# ProPrj___2025-12-14-15-51-23.net
KiCad netlist of a schematic drawn in EasyEDA Pro
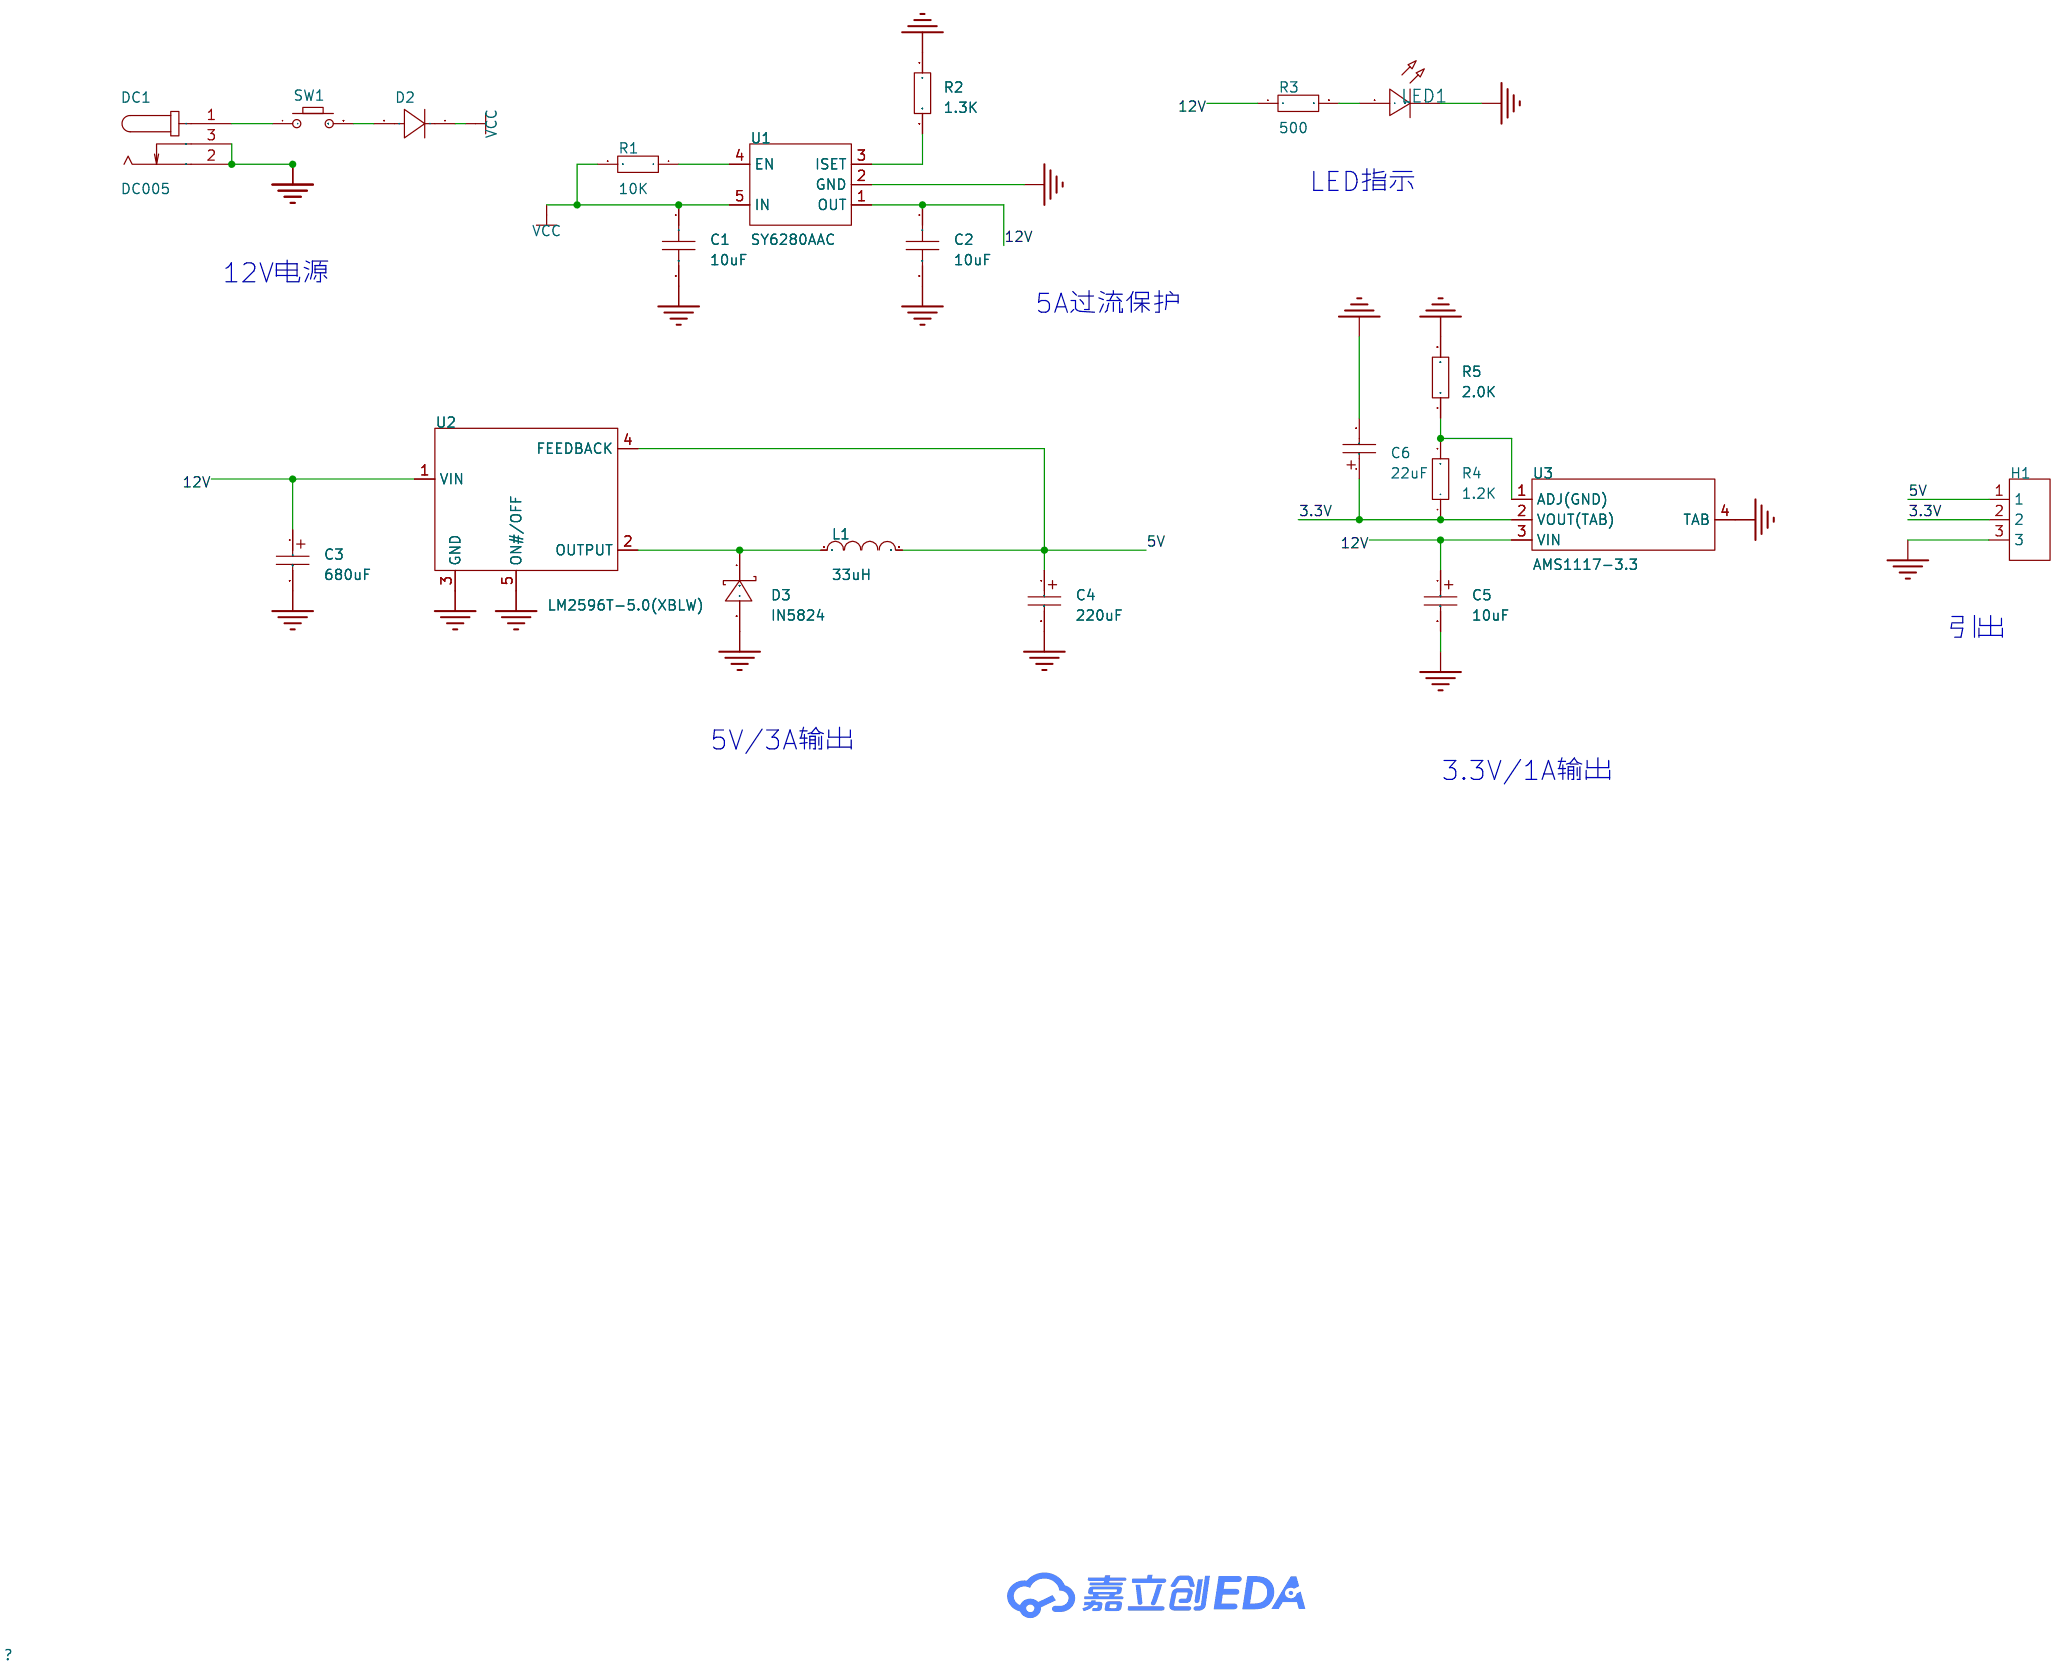
[diagram p0: schematic sheet]

(export (version "E")
  (design (tool "Eeschema 10.0.6"))
  (components
    (comp (ref "C1")
      (value "10uF")
      (footprint "easyedapro:C0603")
      (libsource (lib "easyedapro") (part "Capacitance"))
    )
    (comp (ref "C2")
      (value "10uF")
      (footprint "easyedapro:C0603")
      (libsource (lib "easyedapro") (part "Capacitance"))
    )
    (comp (ref "C3")
      (value "680uF")
      (footprint "easyedapro:C_Ele_SMD_3x5.4mm")
      (libsource (lib "easyedapro") (part "CAP"))
    )
    (comp (ref "C4")
      (value "220uF")
      (footprint "easyedapro:C_Ele_SMD_3x5.4mm")
      (libsource (lib "easyedapro") (part "CAP"))
    )
    (comp (ref "C5")
      (value "10uF")
      (footprint "easyedapro:C_Ele_SMD_3x5.4mm")
      (libsource (lib "easyedapro") (part "CAP"))
    )
    (comp (ref "C6")
      (value "22uF")
      (footprint "easyedapro:C_Ele_SMD_3x5.4mm")
      (libsource (lib "easyedapro") (part "CAP"))
    )
    (comp (ref "D2")
      (value "~")
      (footprint "easyedapro:DO_1N4007")
      (libsource (lib "easyedapro") (part "D_1N4007"))
    )
    (comp (ref "D3")
      (value "IN5824")
      (footprint "easyedapro:SMAF_L3.5-W2.6-LS4.7-RD")
      (libsource (lib "easyedapro") (part "IN5824"))
    )
    (comp (ref "DC1")
      (value "DC005")
      (footprint "easyedapro:DC-IN-TH_DC005")
      (description "连接器类型:DC电源插座;安装方式:弯插;触点内径:2mm;触点外径:6.3mm;额定电流:500mA;额定电压:12V;工作温度:-30°C~+70°C;")
      (fields (field (name "Manufacturer") "SHOU HAN(首韩)"))
      (libsource (lib "easyedapro") (part "DC005_C431533"))
    )
    (comp (ref "H1")
      (value "~")
      (footprint "easyedapro:HDR-TH_3P-P2.54-V-F")
      (libsource (lib "easyedapro") (part "PM254V-11-03-H85"))
    )
    (comp (ref "L1")
      (value "33uH")
      (footprint "easyedapro:L0603")
      (libsource (lib "easyedapro") (part "SDFL1608S100KTF"))
    )
    (comp (ref "LED1")
      (value "~")
      (footprint "easyedapro:LED_0603")
      (libsource (lib "easyedapro") (part "LED_R"))
    )
    (comp (ref "R1") (value "10K") (footprint "easyedapro:R0603") (libsource (lib "easyedapro") (part "电阻")))
    (comp (ref "R2") (value "1.3K") (footprint "easyedapro:R0603") (libsource (lib "easyedapro") (part "电阻")))
    (comp (ref "R3") (value "500") (footprint "easyedapro:R0603") (libsource (lib "easyedapro") (part "电阻")))
    (comp (ref "R4") (value "1.2K") (footprint "easyedapro:R0603") (libsource (lib "easyedapro") (part "电阻")))
    (comp (ref "R5") (value "2.0K") (footprint "easyedapro:R0603") (libsource (lib "easyedapro") (part "电阻")))
    (comp (ref "SW1")
      (value "~")
      (footprint "easyedapro:Key_TH_3.5x6x4.3")
      (libsource (lib "easyedapro") (part "Key_TH_3.5x6x4.3"))
    )
    (comp (ref "U1")
      (value "SY6280AAC")
      (footprint "easyedapro:SOT-23-5_L3.0-W1.7-P0.95-LS2.8-BR")
      (libsource (lib "easyedapro") (part "SY6280AAC_C9900003867"))
    )
    (comp (ref "U2")
      (value "LM2596T-5.0(XBLW)")
      (footprint "easyedapro:TO-220-5L_L10.2-W4.5-P1.71-L")
      (description "功能类型:降压型;工作电压:6V~40V;输出电压:5V;输出电流:3A;输出类型:固定;")
      (fields (field (name "Manufacturer") "XBLW(芯伯乐)"))
      (libsource (lib "easyedapro") (part "LM2596T-5.0(XBLW)"))
    )
    (comp (ref "U3")
      (value "AMS1117-3.3")
      (footprint "easyedapro:SOT-223-4_L6.5-W3.5-P2.30-LS7.0-BR")
      (description "输出类型:固定;工作电压:12V;输出电压:3.3V;输出电流:1A;电源纹波抑制比(PSRR):60dB@(120Hz);输出极性:正极;")
      (fields (field (name "Manufacturer") "UMW(友台半导体)"))
      (libsource (lib "easyedapro") (part "AMS1117-3.3_C347222"))
    )
  )
  (nets
    (net (code "1") (name "/3.3V") (class "Default")
      (node (ref "C6") (pin "1") (pinfunction "1_1") (pintype "input"))
      (node (ref "H1") (pin "2") (pinfunction "2_2") (pintype "unspecified"))
      (node (ref "R4") (pin "1") (pinfunction "1_1") (pintype "input"))
      (node (ref "U3") (pin "2") (pinfunction "VOUT(TAB)_2") (pintype "unspecified"))
    )
    (net (code "2") (name "/5V") (class "Default")
      (node (ref "C4") (pin "1") (pinfunction "1_1") (pintype "input"))
      (node (ref "H1") (pin "1") (pinfunction "1_1") (pintype "unspecified"))
      (node (ref "L1") (pin "2") (pinfunction "2_2") (pintype "unspecified"))
      (node (ref "U2") (pin "4") (pinfunction "FEEDBACK_4") (pintype "unspecified"))
    )
    (net (code "3") (name "/12V") (class "Default")
      (node (ref "C2") (pin "1") (pinfunction "1_1") (pintype "input"))
      (node (ref "C3") (pin "1") (pinfunction "1_1") (pintype "input"))
      (node (ref "C5") (pin "1") (pinfunction "1_1") (pintype "input"))
      (node (ref "R3") (pin "1") (pinfunction "1_1") (pintype "input"))
      (node (ref "U1") (pin "1") (pinfunction "OUT_1") (pintype "unspecified"))
      (node (ref "U2") (pin "1") (pinfunction "VIN_1") (pintype "unspecified"))
      (node (ref "U3") (pin "3") (pinfunction "VIN_3") (pintype "unspecified"))
    )
    (net (code "4") (name "GND") (class "Default")
      (node (ref "C1") (pin "2") (pinfunction "2_2") (pintype "input"))
      (node (ref "C2") (pin "2") (pinfunction "2_2") (pintype "input"))
      (node (ref "C3") (pin "2") (pinfunction "2_2") (pintype "input"))
      (node (ref "C4") (pin "2") (pinfunction "2_2") (pintype "input"))
      (node (ref "C5") (pin "2") (pinfunction "2_2") (pintype "input"))
      (node (ref "C6") (pin "2") (pinfunction "2_2") (pintype "input"))
      (node (ref "D3") (pin "2") (pinfunction "A_2") (pintype "unspecified"))
      (node (ref "DC1") (pin "2") (pinfunction "2_2") (pintype "unspecified"))
      (node (ref "DC1") (pin "3") (pinfunction "3_3") (pintype "unspecified"))
      (node (ref "H1") (pin "3") (pinfunction "3_3") (pintype "unspecified"))
      (node (ref "LED1") (pin "1") (pinfunction "C_1") (pintype "input"))
      (node (ref "R2") (pin "1") (pinfunction "1_1") (pintype "input"))
      (node (ref "R5") (pin "2") (pinfunction "2_2") (pintype "input"))
      (node (ref "U1") (pin "2") (pinfunction "GND_2") (pintype "unspecified"))
      (node (ref "U2") (pin "3") (pinfunction "GND_3") (pintype "unspecified"))
      (node (ref "U2") (pin "5") (pinfunction "ON#/OFF_5") (pintype "unspecified"))
      (node (ref "U3") (pin "4") (pinfunction "TAB_4") (pintype "unspecified"))
    )
    (net (code "5") (name "Net-(D2-A)") (class "Default")
      (node (ref "D2") (pin "2") (pinfunction "A_2") (pintype "input"))
      (node (ref "SW1") (pin "B") (pinfunction "B_B") (pintype "input"))
    )
    (net (code "6") (name "Net-(D3-C)") (class "Default")
      (node (ref "D3") (pin "1") (pinfunction "C_1") (pintype "unspecified"))
      (node (ref "L1") (pin "1") (pinfunction "1_1") (pintype "unspecified"))
      (node (ref "U2") (pin "2") (pinfunction "OUTPUT_2") (pintype "unspecified"))
    )
    (net (code "7") (name "Net-(DC1-Pad1)") (class "Default")
      (node (ref "DC1") (pin "1") (pinfunction "1_1") (pintype "unspecified"))
      (node (ref "SW1") (pin "A") (pinfunction "A_A") (pintype "input"))
    )
    (net (code "8") (name "Net-(LED1-A)") (class "Default")
      (node (ref "LED1") (pin "2") (pinfunction "A_2") (pintype "input"))
      (node (ref "R3") (pin "2") (pinfunction "2_2") (pintype "input"))
    )
    (net (code "9") (name "Net-(U1-EN)") (class "Default")
      (node (ref "R1") (pin "1") (pinfunction "1_1") (pintype "input"))
      (node (ref "U1") (pin "4") (pinfunction "EN_4") (pintype "unspecified"))
    )
    (net (code "10") (name "Net-(U1-ISET)") (class "Default")
      (node (ref "R2") (pin "2") (pinfunction "2_2") (pintype "input"))
      (node (ref "U1") (pin "3") (pinfunction "ISET_3") (pintype "unspecified"))
    )
    (net (code "11") (name "Net-(U3-ADJ(GND))") (class "Default")
      (node (ref "R4") (pin "2") (pinfunction "2_2") (pintype "input"))
      (node (ref "R5") (pin "1") (pinfunction "1_1") (pintype "input"))
      (node (ref "U3") (pin "1") (pinfunction "ADJ(GND)_1") (pintype "unspecified"))
    )
    (net (code "12") (name "VCC") (class "Default")
      (node (ref "C1") (pin "1") (pinfunction "1_1") (pintype "input"))
      (node (ref "D2") (pin "1") (pinfunction "K_1") (pintype "input"))
      (node (ref "R1") (pin "2") (pinfunction "2_2") (pintype "input"))
      (node (ref "U1") (pin "5") (pinfunction "IN_5") (pintype "unspecified"))
    )
  )
)
